# Power_SUM.net
KiCad netlist of a schematic drawn in Altium Designer
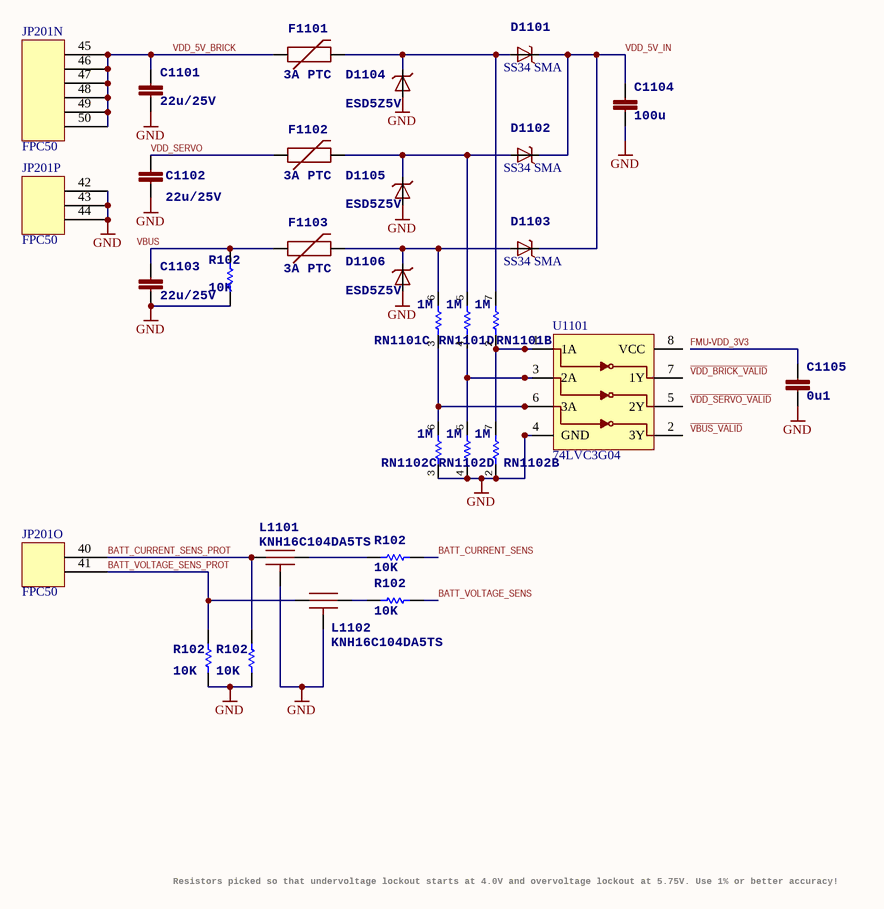
[diagram p0: Power SUM.SchDoc]

(export (version "E")
  (design (tool "Eeschema 10.0.6"))
  (components
    (comp (ref "C1101")
      (value "22u/25V")
      (footprint "0805-CAP")
      (description "<b>Capacitor</b>\nStandard 0603 ceramic capacitor, and 0.1\" leaded capacitor.")
      (fields
        (field (name "PARTNO") "CL21A226MAQNNNE")
        (field (name ">NAME") "C1101")
        (field (name ">VALUE") "22u/25V")
      )
      (libsource (lib "pixhawk2") (part "CAP0805"))
    )
    (comp (ref "C1102")
      (value "22u/25V")
      (footprint "0805-CAP")
      (description "<b>Capacitor</b>\nStandard 0603 ceramic capacitor, and 0.1\" leaded capacitor.")
      (fields
        (field (name "PARTNO") "CL21A226MAQNNNE")
        (field (name ">NAME") "C1102")
        (field (name ">VALUE") "22u/25V")
      )
      (libsource (lib "pixhawk2") (part "CAP0805"))
    )
    (comp (ref "C1103")
      (value "22u/25V")
      (footprint "0805-CAP")
      (description "<b>Capacitor</b>\nStandard 0603 ceramic capacitor, and 0.1\" leaded capacitor.")
      (fields
        (field (name "PARTNO") "CL21A226MAQNNNE")
        (field (name ">NAME") "C1103")
        (field (name ">VALUE") "22u/25V")
      )
      (libsource (lib "pixhawk2") (part "CAP0805"))
    )
    (comp (ref "C1104")
      (value "100u")
      (footprint "1206-CAP")
      (description "<b>Capacitor</b>\nStandard 0603 ceramic capacitor, and 0.1\" leaded capacitor.")
      (fields
        (field (name "PARTNO") "C3216X5R1A107M160AC")
        (field (name ">NAME") "C1104")
        (field (name ">VALUE") "100u")
      )
      (libsource (lib "pixhawk2") (part "CAP1206"))
    )
    (comp (ref "C1105")
      (value "0u1")
      (footprint "0603-CAP")
      (description "<b>Capacitor</b>\nStandard 0603 ceramic capacitor, and 0.1\" leaded capacitor.")
      (fields
        (field (name "PARTNO") "CC0402ZRY5V7BB104")
        (field (name ">NAME") "C1105")
        (field (name ">VALUE") "0u1")
      )
      (libsource (lib "pixhawk2") (part "CAP0402"))
    )
    (comp (ref "D1101")
      (value "SS34 SMA")
      (footprint "SMA")
      (description "Schottky barrier diode in DO214AC, e.g. Fairchild SS14.")
      (libsource (lib "pixhawk2") (part "DIODE-SCHOTTKY_MSMP"))
    )
    (comp (ref "D1102")
      (value "SS34 SMA")
      (footprint "SMA")
      (description "Schottky barrier diode in DO214AC, e.g. Fairchild SS14.")
      (libsource (lib "pixhawk2") (part "DIODE-SCHOTTKY_MSMP"))
    )
    (comp (ref "D1103")
      (value "SS34 SMA")
      (footprint "SMA")
      (description "Schottky barrier diode in DO214AC, e.g. Fairchild SS14.")
      (libsource (lib "pixhawk2") (part "DIODE-SCHOTTKY_MSMP"))
    )
    (comp (ref "D1104")
      (value "ESD5Z5V")
      (footprint "SOD523")
      (libsource (lib "pixhawk2") (part "DIODE-TVS"))
    )
    (comp (ref "D1105")
      (value "ESD5Z5V")
      (footprint "SOD523")
      (libsource (lib "pixhawk2") (part "DIODE-TVS"))
    )
    (comp (ref "D1106")
      (value "ESD5Z5V")
      (footprint "SOD523")
      (libsource (lib "pixhawk2") (part "DIODE-TVS"))
    )
    (comp (ref "F1101")
      (value "3A PTC")
      (footprint "PTC-1206")
      (description "<b>Resettable Fuse PTC</b>\nResettable Fuse. Spark Fun Electronics SKU : COM-08357")
      (fields (field (name ">NAME") "F1101") (field (name ">VALUE") "3A PTC"))
      (libsource (lib "pixhawk2") (part "PTCSMD"))
    )
    (comp (ref "F1102")
      (value "3A PTC")
      (footprint "PTC-1206")
      (description "<b>Resettable Fuse PTC</b>\nResettable Fuse. Spark Fun Electronics SKU : COM-08357")
      (fields (field (name ">NAME") "F1102") (field (name ">VALUE") "3A PTC"))
      (libsource (lib "pixhawk2") (part "PTCSMD"))
    )
    (comp (ref "F1103")
      (value "3A PTC")
      (footprint "PTC-1206")
      (description "<b>Resettable Fuse PTC</b>\nResettable Fuse. Spark Fun Electronics SKU : COM-08357")
      (fields (field (name ">NAME") "F1103") (field (name ">VALUE") "3A PTC"))
      (libsource (lib "pixhawk2") (part "PTCSMD"))
    )
    (comp (ref "JP201") (value "FPC50") (footprint "FPC-0.5-50下接带锁") (libsource (lib "PX4") (part "FPC50")))
    (comp (ref "L1101")
      (value "KNH16C104DA5TS")
      (footprint "KYOCERA-KNH16-DA")
      (description "Kyocera KNH16C104DA5TS EMI filter")
      (libsource (lib "pixhawk2") (part "KNH16C104DA5TS"))
    )
    (comp (ref "L1102")
      (value "KNH16C104DA5TS")
      (footprint "KYOCERA-KNH16-DA")
      (description "Kyocera KNH16C104DA5TS EMI filter")
      (libsource (lib "pixhawk2") (part "KNH16C104DA5TS"))
    )
    (comp (ref "R1101")
      (value "10K")
      (footprint "0603-RES")
      (fields
        (field (name "PARTNO") "RC0402FR-0710KL")
        (field (name ">NAME") "R102")
        (field (name ">VALUE") "10K")
      )
      (libsource (lib "PX4") (part "RESISTOR0402-RES"))
    )
    (comp (ref "R1102")
      (value "10K")
      (footprint "0603-RES")
      (fields
        (field (name "PARTNO") "RC0402FR-0710KL")
        (field (name ">NAME") "R102")
        (field (name ">VALUE") "10K")
      )
      (libsource (lib "PX4") (part "RESISTOR0402-RES"))
    )
    (comp (ref "R1103")
      (value "10K")
      (footprint "0603-RES")
      (fields
        (field (name "PARTNO") "RC0402FR-0710KL")
        (field (name ">NAME") "R102")
        (field (name ">VALUE") "10K")
      )
      (libsource (lib "PX4") (part "RESISTOR0402-RES"))
    )
    (comp (ref "R1104")
      (value "10K")
      (footprint "0603-RES")
      (fields
        (field (name "PARTNO") "RC0402FR-0710KL")
        (field (name ">NAME") "R102")
        (field (name ">VALUE") "10K")
      )
      (libsource (lib "PX4") (part "RESISTOR0402-RES"))
    )
    (comp (ref "R1105")
      (value "10K")
      (footprint "0603-RES")
      (fields
        (field (name "PARTNO") "RC0402FR-0710KL")
        (field (name ">NAME") "R102")
        (field (name ">VALUE") "10K")
      )
      (libsource (lib "PX4") (part "RESISTOR0402-RES"))
    )
    (comp (ref "RN1101")
      (value "1M")
      (footprint "EXB28V")
      (description "<b>Array Chip Resistor</b><p>\nSource: RS Component / Phycomp")
      (fields (field (name "PARTNO") "EXB-28V105JX"))
      (libsource (lib "PX4") (part "4R-NEXB28V"))
    )
    (comp (ref "RN1102")
      (value "1M")
      (footprint "EXB28V")
      (description "<b>Array Chip Resistor</b><p>\nSource: RS Component / Phycomp")
      (fields (field (name "PARTNO") "EXB-28V105JX"))
      (libsource (lib "PX4") (part "4R-NEXB28V"))
    )
    (comp (ref "U1101")
      (value "74LVC3G04")
      (footprint "TSSOP8_SOT505-2")
      (libsource (lib "PX4") (part "74LVC3G04"))
    )
  )
  (nets
    (net (code "1") (name "/BATT_CURRENT_SENS") (class "Default")
      (node (ref "R1101") (pin "P$1") (pinfunction "1_P$1") (pintype "passive"))
    )
    (net (code "2") (name "/BATT_CURRENT_SENS_PROT") (class "Default")
      (node (ref "JP201") (pin "40") (pintype "passive"))
      (node (ref "L1101") (pin "P$1") (pinfunction "P$1_P$1") (pintype "passive"))
      (node (ref "R1104") (pin "P$1") (pinfunction "1_P$1") (pintype "passive"))
    )
    (net (code "3") (name "/BATT_VOLTAGE_SENS") (class "Default")
      (node (ref "R1102") (pin "P$1") (pinfunction "1_P$1") (pintype "passive"))
    )
    (net (code "4") (name "/BATT_VOLTAGE_SENS_PROT") (class "Default")
      (node (ref "JP201") (pin "41") (pintype "passive"))
      (node (ref "L1102") (pin "P$1") (pinfunction "P$1_P$1") (pintype "passive"))
      (node (ref "R1103") (pin "P$1") (pinfunction "1_P$1") (pintype "passive"))
    )
    (net (code "5") (name "/FMU-VDD_3V3") (class "Default")
      (node (ref "C1105") (pin "P$1") (pinfunction "1_P$1") (pintype "passive"))
    )
    (net (code "7") (name "/VDD_5V_BRICK") (class "Default")
      (node (ref "C1101") (pin "P$1") (pinfunction "1_P$1") (pintype "passive"))
      (node (ref "F1101") (pin "1") (pinfunction "1_1") (pintype "passive"))
      (node (ref "JP201") (pin "45") (pintype "passive"))
      (node (ref "JP201") (pin "46") (pintype "passive"))
      (node (ref "JP201") (pin "47") (pintype "passive"))
      (node (ref "JP201") (pin "48") (pintype "passive"))
      (node (ref "JP201") (pin "49") (pintype "passive"))
      (node (ref "JP201") (pin "50") (pintype "passive"))
    )
    (net (code "8") (name "/VDD_5V_IN") (class "Default")
      (node (ref "C1104") (pin "P$1") (pinfunction "1_P$1") (pintype "passive"))
      (node (ref "D1101") (pin "C") (pinfunction "C_C") (pintype "passive"))
      (node (ref "D1102") (pin "C") (pinfunction "C_C") (pintype "passive"))
      (node (ref "D1103") (pin "C") (pinfunction "C_C") (pintype "passive"))
    )
    (net (code "9") (name "/VDD_SERVO") (class "Default")
      (node (ref "C1102") (pin "P$1") (pinfunction "1_P$1") (pintype "passive"))
      (node (ref "F1102") (pin "1") (pinfunction "1_1") (pintype "passive"))
    )
    (net (code "13") (name "GND") (class "Default")
      (node (ref "C1101") (pin "P$2") (pinfunction "2_P$2") (pintype "passive"))
      (node (ref "C1102") (pin "P$2") (pinfunction "2_P$2") (pintype "passive"))
      (node (ref "C1103") (pin "P$2") (pinfunction "2_P$2") (pintype "passive"))
      (node (ref "C1104") (pin "P$2") (pinfunction "2_P$2") (pintype "passive"))
      (node (ref "C1105") (pin "P$2") (pinfunction "2_P$2") (pintype "passive"))
      (node (ref "D1104") (pin "A") (pinfunction "A_A") (pintype "passive"))
      (node (ref "D1105") (pin "A") (pinfunction "A_A") (pintype "passive"))
      (node (ref "D1106") (pin "A") (pinfunction "A_A") (pintype "passive"))
      (node (ref "JP201") (pin "42") (pintype "passive"))
      (node (ref "JP201") (pin "43") (pintype "passive"))
      (node (ref "JP201") (pin "44") (pintype "passive"))
      (node (ref "L1101") (pin "P$3_P$4_P$5") (pinfunction "P$3_P$4_P$5_P$3_P$4_P$5") (pintype "passive"))
      (node (ref "L1102") (pin "P$3_P$4_P$5") (pinfunction "P$3_P$4_P$5_P$3_P$4_P$5") (pintype "passive"))
      (node (ref "R1103") (pin "P$2") (pinfunction "2_P$2") (pintype "passive"))
      (node (ref "R1104") (pin "P$2") (pinfunction "2_P$2") (pintype "passive"))
      (node (ref "R1105") (pin "P$2") (pinfunction "2_P$2") (pintype "passive"))
      (node (ref "RN1102") (pin "2") (pinfunction "1_2") (pintype "passive"))
      (node (ref "RN1102") (pin "3") (pinfunction "1_3") (pintype "passive"))
      (node (ref "RN1102") (pin "4") (pinfunction "1_4") (pintype "passive"))
      (node (ref "U1101") (pin "4") (pinfunction "GND_4") (pintype "open_emitter"))
    )
    (net (code "14") (name "Net-(C1103-1)") (class "Default")
      (node (ref "C1103") (pin "P$1") (pinfunction "1_P$1") (pintype "passive"))
      (node (ref "F1103") (pin "1") (pinfunction "1_1") (pintype "passive"))
      (node (ref "R1105") (pin "P$1") (pinfunction "1_P$1") (pintype "passive"))
    )
    (net (code "15") (name "Net-(R1101-2)") (class "Default")
      (node (ref "L1101") (pin "P$2") (pinfunction "P$2_P$2") (pintype "passive"))
      (node (ref "R1101") (pin "P$2") (pinfunction "2_P$2") (pintype "passive"))
    )
    (net (code "16") (name "Net-(R1102-2)") (class "Default")
      (node (ref "L1102") (pin "P$2") (pinfunction "P$2_P$2") (pintype "passive"))
      (node (ref "R1102") (pin "P$2") (pinfunction "2_P$2") (pintype "passive"))
    )
    (net (code "17") (name "Net-(RN1101B-1)") (class "Default")
      (node (ref "RN1101") (pin "2") (pinfunction "1_2") (pintype "passive"))
      (node (ref "RN1102") (pin "7") (pinfunction "2_7") (pintype "passive"))
      (node (ref "U1101") (pin "1") (pinfunction "1A_1") (pintype "passive"))
    )
    (net (code "18") (name "Net-(RN1101B-2)") (class "Default")
      (node (ref "D1101") (pin "A") (pinfunction "A_A") (pintype "passive"))
      (node (ref "D1104") (pin "C") (pinfunction "C_C") (pintype "passive"))
      (node (ref "F1101") (pin "2") (pinfunction "2_2") (pintype "passive"))
      (node (ref "RN1101") (pin "7") (pinfunction "2_7") (pintype "passive"))
    )
    (net (code "19") (name "Net-(RN1101C-1)") (class "Default")
      (node (ref "RN1101") (pin "3") (pinfunction "1_3") (pintype "passive"))
      (node (ref "RN1102") (pin "6") (pinfunction "2_6") (pintype "passive"))
      (node (ref "U1101") (pin "6") (pinfunction "3A_6") (pintype "passive"))
    )
    (net (code "20") (name "Net-(RN1101C-2)") (class "Default")
      (node (ref "D1103") (pin "A") (pinfunction "A_A") (pintype "passive"))
      (node (ref "D1106") (pin "C") (pinfunction "C_C") (pintype "passive"))
      (node (ref "F1103") (pin "2") (pinfunction "2_2") (pintype "passive"))
      (node (ref "RN1101") (pin "6") (pinfunction "2_6") (pintype "passive"))
    )
    (net (code "21") (name "Net-(RN1101D-1)") (class "Default")
      (node (ref "RN1101") (pin "4") (pinfunction "1_4") (pintype "passive"))
      (node (ref "RN1102") (pin "5") (pinfunction "2_5") (pintype "passive"))
      (node (ref "U1101") (pin "3") (pinfunction "2A_3") (pintype "passive"))
    )
    (net (code "22") (name "Net-(RN1101D-2)") (class "Default")
      (node (ref "D1102") (pin "A") (pinfunction "A_A") (pintype "passive"))
      (node (ref "D1105") (pin "C") (pinfunction "C_C") (pintype "passive"))
      (node (ref "F1102") (pin "2") (pinfunction "2_2") (pintype "passive"))
      (node (ref "RN1101") (pin "5") (pinfunction "2_5") (pintype "passive"))
    )
    (net (code "23") (name "unconnected-(U1101-1Y-Pad7)") (class "Default")
      (node (ref "U1101") (pin "7") (pinfunction "1Y_7") (pintype "passive"))
    )
    (net (code "24") (name "unconnected-(U1101-2Y-Pad5)") (class "Default")
      (node (ref "U1101") (pin "5") (pinfunction "2Y_5") (pintype "passive"))
    )
    (net (code "25") (name "unconnected-(U1101-3Y-Pad2)") (class "Default")
      (node (ref "U1101") (pin "2") (pinfunction "3Y_2") (pintype "passive"))
    )
    (net (code "26") (name "unconnected-(U1101-VCC-Pad8)") (class "Default")
      (node (ref "U1101") (pin "8") (pinfunction "VCC_8") (pintype "open_emitter"))
    )
  )
)
